# m101-psu-dcdc.net
KiCad netlist of a schematic drawn in EAGLE
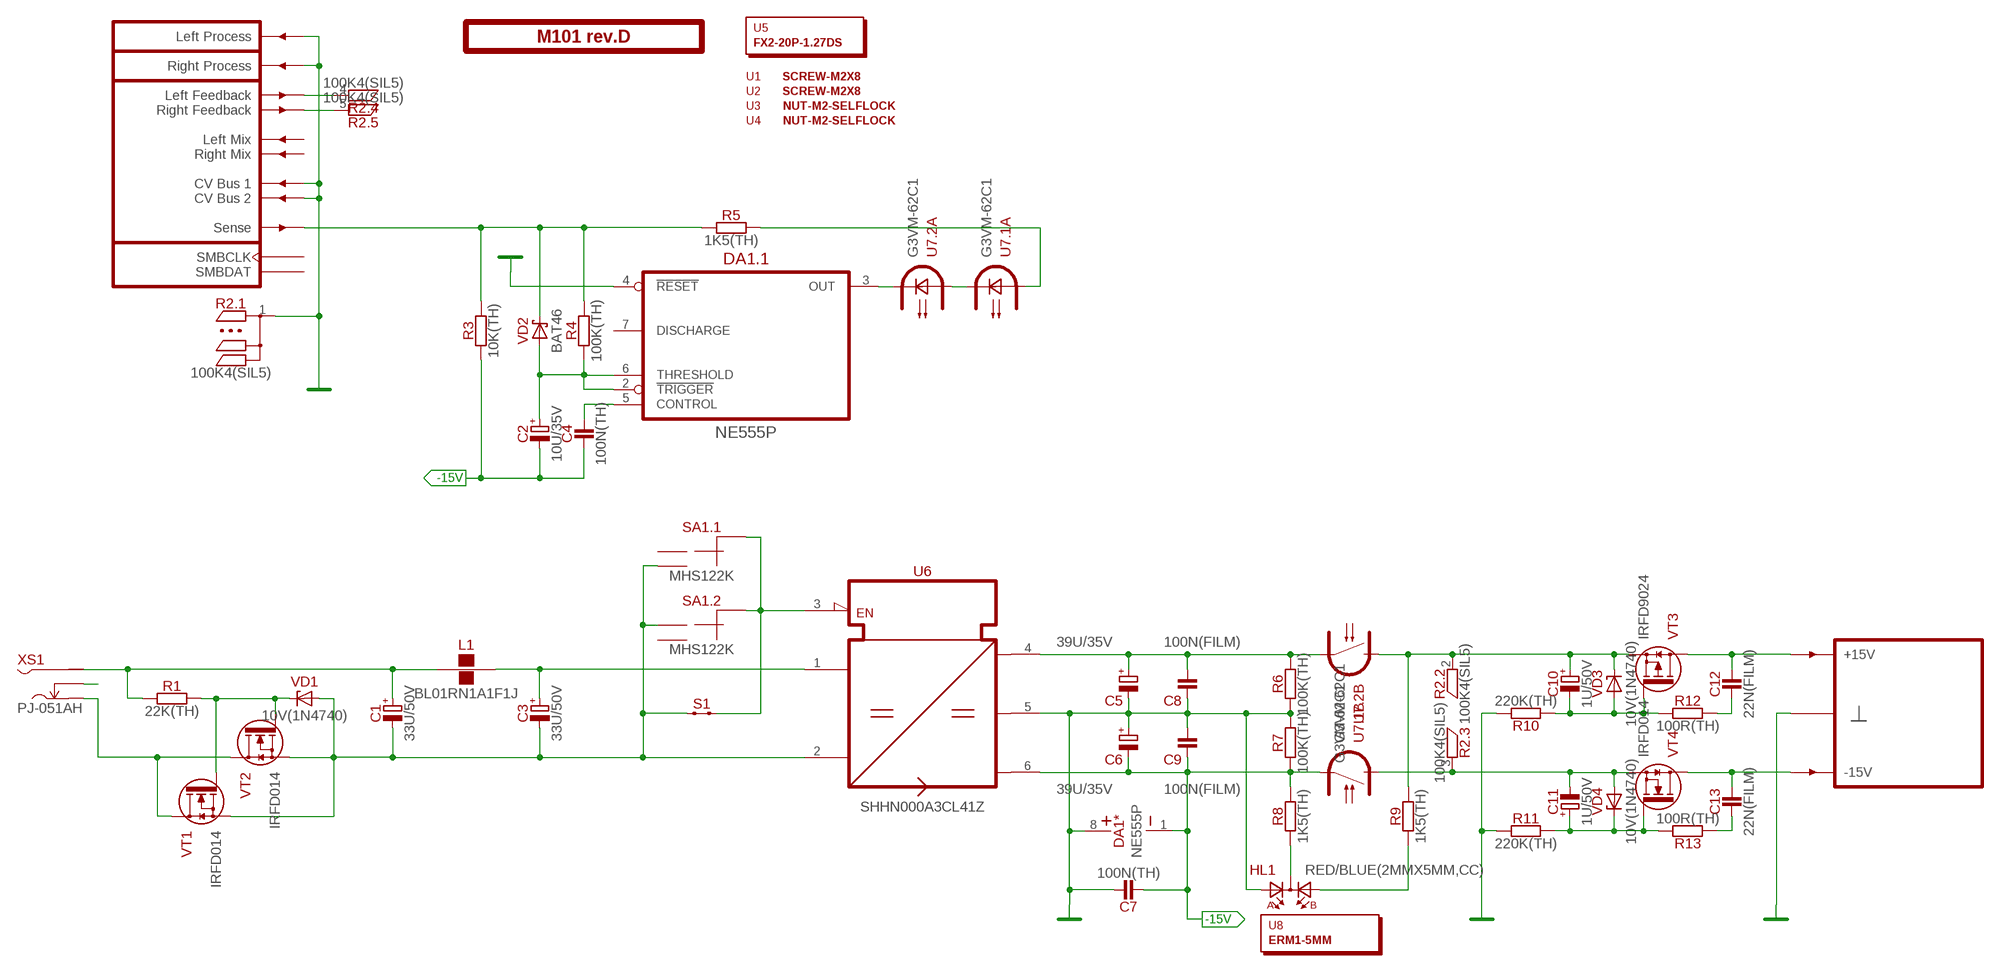
[diagram p0: schematic, sheet 1]

(export (version "E")
  (design (tool "Eeschema 10.0.6"))
  (components
    (comp (ref "C1")
      (value "33U/50V")
      (footprint "eagle-import:E3,5-8")
      (libsource (lib "eagle-import") (part "?33U/50V"))
    )
    (comp (ref "C2")
      (value "10U/35V")
      (footprint "eagle-import:E2-5")
      (libsource (lib "eagle-import") (part "?10U/35V"))
    )
    (comp (ref "C3")
      (value "33U/50V")
      (footprint "eagle-import:E3,5-8")
      (libsource (lib "eagle-import") (part "?33U/50V"))
    )
    (comp (ref "C4")
      (value "100N(TH)")
      (footprint "eagle-import:C050-024X044")
      (libsource (lib "eagle-import") (part "?100N(TH)"))
    )
    (comp (ref "C5")
      (value "39U/35V")
      (footprint "eagle-import:E3,5-8")
      (libsource (lib "eagle-import") (part "?39U/35V"))
    )
    (comp (ref "C6")
      (value "39U/35V")
      (footprint "eagle-import:E3,5-8")
      (libsource (lib "eagle-import") (part "?39U/35V"))
    )
    (comp (ref "C7")
      (value "100N(TH)")
      (footprint "eagle-import:C050-024X044")
      (libsource (lib "eagle-import") (part "?100N(TH)"))
    )
    (comp (ref "C8")
      (value "100N(FILM)")
      (footprint "eagle-import:C050-025X075")
      (libsource (lib "eagle-import") (part "?100N(FILM)"))
    )
    (comp (ref "C9")
      (value "100N(FILM)")
      (footprint "eagle-import:C050-025X075")
      (libsource (lib "eagle-import") (part "?100N(FILM)"))
    )
    (comp (ref "C10")
      (value "1U/50V")
      (footprint "eagle-import:E1,5-4")
      (libsource (lib "eagle-import") (part "?1U/50V"))
    )
    (comp (ref "C11")
      (value "1U/50V")
      (footprint "eagle-import:E1,5-4")
      (libsource (lib "eagle-import") (part "?1U/50V"))
    )
    (comp (ref "C12")
      (value "22N(FILM)")
      (footprint "eagle-import:C050-025X075")
      (libsource (lib "eagle-import") (part "?22N(FILM)"))
    )
    (comp (ref "C13")
      (value "22N(FILM)")
      (footprint "eagle-import:C050-025X075")
      (libsource (lib "eagle-import") (part "?22N(FILM)"))
    )
    (comp (ref "DA1")
      (value "NE555P")
      (footprint "eagle-import:DIP-8")
      (libsource (lib "eagle-import") (part "NE555?P"))
    )
    (comp (ref "HL1")
      (value "RED/BLUE(2MMX5MM,CC)")
      (footprint "eagle-import:LED2X5-3PIN")
      (libsource (lib "eagle-import") (part "?(2MMX5MM,CC)RED/BLUE"))
    )
    (comp (ref "L1")
      (value "BL01RN1A1F1J")
      (footprint "eagle-import:BL01RN1A")
      (libsource (lib "eagle-import") (part "BL01RN1A?1F1J"))
    )
    (comp (ref "PCB1")
      (value "M101 rev.D")
      (footprint "eagle-import:ST2-BOARD-50-PSU")
      (libsource (lib "eagle-import") (part "ST2-BOARD-50-PSU"))
    )
    (comp (ref "R1")
      (value "22K(TH)")
      (footprint "eagle-import:R-0207_10")
      (libsource (lib "eagle-import") (part "?22K(TH)"))
    )
    (comp (ref "R2")
      (value "100K4(SIL5)")
      (footprint "eagle-import:R-SIL5")
      (libsource (lib "eagle-import") (part "?4(SIL5)100K"))
    )
    (comp (ref "R3")
      (value "10K(TH)")
      (footprint "eagle-import:R-0207_10")
      (libsource (lib "eagle-import") (part "?10K(TH)"))
    )
    (comp (ref "R4")
      (value "100K(TH)")
      (footprint "eagle-import:R-0207_10")
      (libsource (lib "eagle-import") (part "?100K(TH)"))
    )
    (comp (ref "R5")
      (value "1K5(TH)")
      (footprint "eagle-import:R-0207_10")
      (libsource (lib "eagle-import") (part "?1K5(TH)"))
    )
    (comp (ref "R6")
      (value "100K(TH)")
      (footprint "eagle-import:R-0207_10")
      (libsource (lib "eagle-import") (part "?100K(TH)"))
    )
    (comp (ref "R7")
      (value "100K(TH)")
      (footprint "eagle-import:R-0207_10")
      (libsource (lib "eagle-import") (part "?100K(TH)"))
    )
    (comp (ref "R8")
      (value "1K5(TH)")
      (footprint "eagle-import:R-0207_10")
      (libsource (lib "eagle-import") (part "?1K5(TH)"))
    )
    (comp (ref "R9")
      (value "1K5(TH)")
      (footprint "eagle-import:R-0207_10")
      (libsource (lib "eagle-import") (part "?1K5(TH)"))
    )
    (comp (ref "R10")
      (value "220K(TH)")
      (footprint "eagle-import:R-0207_10")
      (libsource (lib "eagle-import") (part "?220K(TH)"))
    )
    (comp (ref "R11")
      (value "220K(TH)")
      (footprint "eagle-import:R-0207_10")
      (libsource (lib "eagle-import") (part "?220K(TH)"))
    )
    (comp (ref "R12")
      (value "100R(TH)")
      (footprint "eagle-import:R-0207_10")
      (libsource (lib "eagle-import") (part "?100R(TH)"))
    )
    (comp (ref "R13")
      (value "100R(TH)")
      (footprint "eagle-import:R-0207_10")
      (libsource (lib "eagle-import") (part "?100R(TH)"))
    )
    (comp (ref "S1")
      (value "JUMPER-1POS-SOLDER")
      (footprint "eagle-import:JP1-SOLDER")
      (libsource (lib "eagle-import") (part "JUMPER-1POS-SOLDER"))
    )
    (comp (ref "SA1")
      (value "MHS122K")
      (footprint "eagle-import:APEM-MHS122K")
      (libsource (lib "eagle-import") (part "MHS122K"))
    )
    (comp (ref "U1")
      (value "SCREW-M2X8")
      (footprint "eagle-import:EMPTY")
      (libsource (lib "eagle-import") (part "?SCREW-M2X8"))
    )
    (comp (ref "U2")
      (value "SCREW-M2X8")
      (footprint "eagle-import:EMPTY")
      (libsource (lib "eagle-import") (part "?SCREW-M2X8"))
    )
    (comp (ref "U3")
      (value "NUT-M2-SELFLOCK")
      (footprint "eagle-import:EMPTY")
      (libsource (lib "eagle-import") (part "?NUT-M2-SELFLOCK"))
    )
    (comp (ref "U4")
      (value "NUT-M2-SELFLOCK")
      (footprint "eagle-import:EMPTY")
      (libsource (lib "eagle-import") (part "?NUT-M2-SELFLOCK"))
    )
    (comp (ref "U5")
      (value "FX2-20P-1.27DS")
      (footprint "eagle-import:EMPTY")
      (libsource (lib "eagle-import") (part "?FX2-20P-1.27DS"))
    )
    (comp (ref "U6")
      (value "SHHN000A3CL41Z")
      (footprint "eagle-import:DC_DC-C1")
      (libsource (lib "eagle-import") (part "SHHN000A3CL41Z"))
    )
    (comp (ref "U7")
      (value "G3VM-62C1")
      (footprint "eagle-import:DIL08")
      (libsource (lib "eagle-import") (part "G3VM-?2C61"))
    )
    (comp (ref "U8")
      (value "ERM1-5MM")
      (footprint "eagle-import:EMPTY")
      (libsource (lib "eagle-import") (part "?ERM1-5MM"))
    )
    (comp (ref "VD1")
      (value "10V(1N4740)")
      (footprint "eagle-import:DO41-10")
      (libsource (lib "eagle-import") (part "?10V(1N4740)"))
    )
    (comp (ref "VD2")
      (value "BAT46")
      (footprint "eagle-import:DO35-7")
      (libsource (lib "eagle-import") (part "?BAT46"))
    )
    (comp (ref "VD3")
      (value "10V(1N4740)")
      (footprint "eagle-import:DO41-10")
      (libsource (lib "eagle-import") (part "?10V(1N4740)"))
    )
    (comp (ref "VD4")
      (value "10V(1N4740)")
      (footprint "eagle-import:DO41-10")
      (libsource (lib "eagle-import") (part "?10V(1N4740)"))
    )
    (comp (ref "VT1")
      (value "IRFD014")
      (footprint "eagle-import:HVMDIP-4")
      (libsource (lib "eagle-import") (part "IRFD014"))
    )
    (comp (ref "VT2")
      (value "IRFD014")
      (footprint "eagle-import:HVMDIP-4")
      (libsource (lib "eagle-import") (part "IRFD014"))
    )
    (comp (ref "VT3")
      (value "IRFD9024")
      (footprint "eagle-import:HVMDIP-4")
      (libsource (lib "eagle-import") (part "IRFD9024"))
    )
    (comp (ref "VT4")
      (value "IRFD014")
      (footprint "eagle-import:HVMDIP-4")
      (libsource (lib "eagle-import") (part "IRFD014"))
    )
    (comp (ref "XS1")
      (value "PJ-051AH")
      (footprint "eagle-import:PJ-051AH")
      (libsource (lib "eagle-import") (part "PJ-051?AH"))
    )
  )
  (nets
    (net (code "1") (name "-15V") (class "Default")
      (node (ref "C2") (pin "-") (pinfunction "-_-") (pintype "passive"))
      (node (ref "C4") (pin "1") (pinfunction "1_1") (pintype "passive"))
      (node (ref "C6") (pin "-") (pinfunction "-_-") (pintype "passive"))
      (node (ref "C7") (pin "1") (pinfunction "1_1") (pintype "passive"))
      (node (ref "C9") (pin "1") (pinfunction "1_1") (pintype "passive"))
      (node (ref "DA1") (pin "1") (pinfunction "V-_1") (pintype "power_in"))
      (node (ref "R3") (pin "1") (pinfunction "1_1") (pintype "passive"))
      (node (ref "R7") (pin "1") (pinfunction "1_1") (pintype "passive"))
      (node (ref "R8") (pin "2") (pinfunction "2_2") (pintype "passive"))
      (node (ref "U6") (pin "6") (pinfunction "V-_6") (pintype "power_in"))
      (node (ref "U7") (pin "7") (pinfunction "S2_7") (pintype "passive"))
    )
    (net (code "2") (name "GND") (class "Default")
      (node (ref "C5") (pin "-") (pinfunction "-_-") (pintype "passive"))
      (node (ref "C6") (pin "+") (pinfunction "+_+") (pintype "passive"))
      (node (ref "C7") (pin "2") (pinfunction "2_2") (pintype "passive"))
      (node (ref "C8") (pin "1") (pinfunction "1_1") (pintype "passive"))
      (node (ref "C9") (pin "2") (pinfunction "2_2") (pintype "passive"))
      (node (ref "DA1") (pin "4") (pinfunction "~{RESET}_4") (pintype "input"))
      (node (ref "DA1") (pin "8") (pinfunction "V+_8") (pintype "power_in"))
      (node (ref "HL1") (pin "A1") (pinfunction "A1_A1") (pintype "passive"))
      (node (ref "PCB1") (pin "ACV1'") (pinfunction "CV1'_ACV1'") (pintype "bidirectional"))
      (node (ref "PCB1") (pin "ACV2'") (pinfunction "CV2'_ACV2'") (pintype "bidirectional"))
      (node (ref "PCB1") (pin "B4'") (pinfunction "GND_B4'") (pintype "bidirectional"))
      (node (ref "PCB1") (pin "B5'") (pinfunction "GND_B5'") (pintype "bidirectional"))
      (node (ref "PCB1") (pin "B6'") (pinfunction "GND_B6'") (pintype "bidirectional"))
      (node (ref "PCB1") (pin "B7'") (pinfunction "GND_B7'") (pintype "bidirectional"))
      (node (ref "PCB1") (pin "B8'") (pinfunction "GND_B8'") (pintype "bidirectional"))
      (node (ref "PCB1") (pin "BOUTL'") (pinfunction "OUTL_BOUTL'") (pintype "bidirectional"))
      (node (ref "PCB1") (pin "BOUTR'") (pinfunction "OUTR_BOUTR'") (pintype "bidirectional"))
      (node (ref "R10") (pin "2") (pinfunction "2_2") (pintype "passive"))
      (node (ref "R11") (pin "2") (pinfunction "2_2") (pintype "passive"))
      (node (ref "R2") (pin "1") (pinfunction "R_1") (pintype "passive"))
      (node (ref "R6") (pin "1") (pinfunction "1_1") (pintype "passive"))
      (node (ref "R7") (pin "2") (pinfunction "2_2") (pintype "passive"))
      (node (ref "U6") (pin "5") (pinfunction "GND_5") (pintype "power_in"))
    )
    (net (code "3") (name "Net-(C12-Pad1)") (class "Default")
      (node (ref "C12") (pin "1") (pinfunction "1_1") (pintype "passive"))
      (node (ref "R12") (pin "2") (pinfunction "2_2") (pintype "passive"))
    )
    (net (code "4") (name "Net-(C12-Pad2)") (class "Default")
      (node (ref "C12") (pin "2") (pinfunction "2_2") (pintype "passive"))
      (node (ref "PCB1") (pin "A+15'") (pinfunction "P+15V_A+15'") (pintype "bidirectional"))
      (node (ref "PCB1") (pin "B+15'") (pinfunction "P+15V_B+15'") (pintype "bidirectional"))
      (node (ref "VT3") (pin "1") (pinfunction "D_1") (pintype "bidirectional"))
      (node (ref "VT3") (pin "2") (pinfunction "D_2") (pintype "bidirectional"))
    )
    (net (code "5") (name "Net-(C13-Pad1)") (class "Default")
      (node (ref "C13") (pin "1") (pinfunction "1_1") (pintype "passive"))
      (node (ref "PCB1") (pin "A-15'") (pinfunction "P-15V_A-15'") (pintype "bidirectional"))
      (node (ref "PCB1") (pin "B-15'") (pinfunction "P-15V_B-15'") (pintype "bidirectional"))
      (node (ref "VT4") (pin "1") (pinfunction "D_1") (pintype "bidirectional"))
      (node (ref "VT4") (pin "2") (pinfunction "D_2") (pintype "bidirectional"))
    )
    (net (code "6") (name "Net-(C13-Pad2)") (class "Default")
      (node (ref "C13") (pin "2") (pinfunction "2_2") (pintype "passive"))
      (node (ref "R13") (pin "2") (pinfunction "2_2") (pintype "passive"))
    )
    (net (code "7") (name "Net-(DA1B-CONTROL)") (class "Default")
      (node (ref "C4") (pin "2") (pinfunction "2_2") (pintype "passive"))
      (node (ref "DA1") (pin "5") (pinfunction "CONTROL_5") (pintype "bidirectional"))
    )
    (net (code "8") (name "Net-(DA1B-OUT)") (class "Default")
      (node (ref "DA1") (pin "3") (pinfunction "OUT_3") (pintype "bidirectional"))
      (node (ref "U7") (pin "4") (pinfunction "C_4") (pintype "passive"))
    )
    (net (code "9") (name "Net-(DA1B-THRESHOLD)") (class "Default")
      (node (ref "C2") (pin "+") (pinfunction "+_+") (pintype "passive"))
      (node (ref "DA1") (pin "2") (pinfunction "~{TRIGGER}_2") (pintype "bidirectional"))
      (node (ref "DA1") (pin "6") (pinfunction "THRESHOLD_6") (pintype "bidirectional"))
      (node (ref "R4") (pin "1") (pinfunction "1_1") (pintype "passive"))
      (node (ref "VD2") (pin "A") (pinfunction "A_A") (pintype "passive"))
    )
    (net (code "10") (name "Net-(HL1-PadA2)") (class "Default")
      (node (ref "HL1") (pin "A2") (pinfunction "A2_A2") (pintype "passive"))
      (node (ref "R9") (pin "1") (pinfunction "1_1") (pintype "passive"))
    )
    (net (code "11") (name "Net-(HL1-PadK)") (class "Default")
      (node (ref "HL1") (pin "K") (pinfunction "K_K") (pintype "passive"))
      (node (ref "R8") (pin "1") (pinfunction "1_1") (pintype "passive"))
    )
    (net (code "12") (name "Net-(PCB1D-LFBK')") (class "Default")
      (node (ref "PCB1") (pin "ALFBK'") (pinfunction "LFBK'_ALFBK'") (pintype "bidirectional"))
      (node (ref "R2") (pin "4") (pinfunction "R_4") (pintype "passive"))
    )
    (net (code "13") (name "Net-(PCB1D-RFBK')") (class "Default")
      (node (ref "PCB1") (pin "ARFBK'") (pinfunction "RFBK'_ARFBK'") (pintype "bidirectional"))
      (node (ref "R2") (pin "5") (pinfunction "R_5") (pintype "passive"))
    )
    (net (code "14") (name "Net-(PCB1D-SENSE')") (class "Default")
      (node (ref "PCB1") (pin "BSENSE'") (pinfunction "SENSE'_BSENSE'") (pintype "bidirectional"))
      (node (ref "R3") (pin "2") (pinfunction "2_2") (pintype "passive"))
      (node (ref "R4") (pin "2") (pinfunction "2_2") (pintype "passive"))
      (node (ref "R5") (pin "1") (pinfunction "1_1") (pintype "passive"))
      (node (ref "VD2") (pin "C") (pinfunction "C_C") (pintype "passive"))
    )
    (net (code "15") (name "Net-(R2B-R)") (class "Default")
      (node (ref "C10") (pin "+") (pinfunction "+_+") (pintype "passive"))
      (node (ref "R2") (pin "2") (pinfunction "R_2") (pintype "passive"))
      (node (ref "R9") (pin "2") (pinfunction "2_2") (pintype "passive"))
      (node (ref "U7") (pin "6") (pinfunction "S1_6") (pintype "passive"))
      (node (ref "VD3") (pin "C") (pinfunction "C_C") (pintype "passive"))
      (node (ref "VT3") (pin "4") (pinfunction "S_4") (pintype "bidirectional"))
    )
    (net (code "16") (name "Net-(R2C-R)") (class "Default")
      (node (ref "C11") (pin "-") (pinfunction "-_-") (pintype "passive"))
      (node (ref "R2") (pin "3") (pinfunction "R_3") (pintype "passive"))
      (node (ref "U7") (pin "8") (pinfunction "S1_8") (pintype "passive"))
      (node (ref "VD4") (pin "A") (pinfunction "A_A") (pintype "passive"))
      (node (ref "VT4") (pin "4") (pinfunction "S_4") (pintype "bidirectional"))
    )
    (net (code "17") (name "Net-(SA1A-CM)") (class "Default")
      (node (ref "S1") (pin "2") (pinfunction "2_2") (pintype "passive"))
      (node (ref "SA1") (pin "CMN") (pinfunction "CM_CMN") (pintype "passive"))
      (node (ref "SA1") (pin "CMN'") (pinfunction "CM_CMN'") (pintype "passive"))
      (node (ref "U6") (pin "3") (pinfunction "EN_3") (pintype "bidirectional"))
    )
    (net (code "18") (name "Net-(SA1B-1)") (class "Default")
      (node (ref "C1") (pin "-") (pinfunction "-_-") (pintype "passive"))
      (node (ref "C3") (pin "-") (pinfunction "-_-") (pintype "passive"))
      (node (ref "S1") (pin "1") (pinfunction "1_1") (pintype "passive"))
      (node (ref "SA1") (pin "1'") (pinfunction "1_1'") (pintype "passive"))
      (node (ref "SA1") (pin "2") (pinfunction "2_2") (pintype "passive"))
      (node (ref "U6") (pin "2") (pinfunction "IN-_2") (pintype "power_in"))
      (node (ref "VD1") (pin "A") (pinfunction "A_A") (pintype "passive"))
      (node (ref "VT1") (pin "4") (pinfunction "S_4") (pintype "bidirectional"))
      (node (ref "VT2") (pin "4") (pinfunction "S_4") (pintype "bidirectional"))
    )
    (net (code "19") (name "Net-(U6-IN+)") (class "Default")
      (node (ref "C3") (pin "+") (pinfunction "+_+") (pintype "passive"))
      (node (ref "L1") (pin "2") (pinfunction "2_2") (pintype "passive"))
      (node (ref "U6") (pin "1") (pinfunction "IN+_1") (pintype "power_in"))
    )
    (net (code "20") (name "Net-(U6-V+)") (class "Default")
      (node (ref "C5") (pin "+") (pinfunction "+_+") (pintype "passive"))
      (node (ref "C8") (pin "2") (pinfunction "2_2") (pintype "passive"))
      (node (ref "R6") (pin "2") (pinfunction "2_2") (pintype "passive"))
      (node (ref "U6") (pin "4") (pinfunction "V+_4") (pintype "power_in"))
      (node (ref "U7") (pin "5") (pinfunction "S2_5") (pintype "passive"))
    )
    (net (code "21") (name "Net-(U7A-A)") (class "Default")
      (node (ref "R5") (pin "2") (pinfunction "2_2") (pintype "passive"))
      (node (ref "U7") (pin "1") (pinfunction "A_1") (pintype "passive"))
    )
    (net (code "22") (name "Net-(U7A-C)") (class "Default")
      (node (ref "U7") (pin "2") (pinfunction "C_2") (pintype "passive"))
      (node (ref "U7") (pin "3") (pinfunction "A_3") (pintype "passive"))
    )
    (net (code "23") (name "Net-(VT1-G)") (class "Default")
      (node (ref "R1") (pin "2") (pinfunction "2_2") (pintype "passive"))
      (node (ref "VD1") (pin "C") (pinfunction "C_C") (pintype "passive"))
      (node (ref "VT1") (pin "3") (pinfunction "G_3") (pintype "bidirectional"))
      (node (ref "VT2") (pin "3") (pinfunction "G_3") (pintype "bidirectional"))
    )
    (net (code "24") (name "Net-(VT3-G)") (class "Default")
      (node (ref "C10") (pin "-") (pinfunction "-_-") (pintype "passive"))
      (node (ref "R10") (pin "1") (pinfunction "1_1") (pintype "passive"))
      (node (ref "R12") (pin "1") (pinfunction "1_1") (pintype "passive"))
      (node (ref "VD3") (pin "A") (pinfunction "A_A") (pintype "passive"))
      (node (ref "VT3") (pin "3") (pinfunction "G_3") (pintype "bidirectional"))
    )
    (net (code "25") (name "Net-(VT4-G)") (class "Default")
      (node (ref "C11") (pin "+") (pinfunction "+_+") (pintype "passive"))
      (node (ref "R11") (pin "1") (pinfunction "1_1") (pintype "passive"))
      (node (ref "R13") (pin "1") (pinfunction "1_1") (pintype "passive"))
      (node (ref "VD4") (pin "C") (pinfunction "C_C") (pintype "passive"))
      (node (ref "VT4") (pin "3") (pinfunction "G_3") (pintype "bidirectional"))
    )
    (net (code "26") (name "Net-(XS1-P)") (class "Default")
      (node (ref "C1") (pin "+") (pinfunction "+_+") (pintype "passive"))
      (node (ref "L1") (pin "1") (pinfunction "1_1") (pintype "passive"))
      (node (ref "R1") (pin "1") (pinfunction "1_1") (pintype "passive"))
      (node (ref "XS1") (pin "1") (pinfunction "P_1") (pintype "passive"))
    )
    (net (code "27") (name "Net-(XS1-S)") (class "Default")
      (node (ref "VT1") (pin "1") (pinfunction "D_1") (pintype "bidirectional"))
      (node (ref "VT1") (pin "2") (pinfunction "D_2") (pintype "bidirectional"))
      (node (ref "VT2") (pin "1") (pinfunction "D_1") (pintype "bidirectional"))
      (node (ref "VT2") (pin "2") (pinfunction "D_2") (pintype "bidirectional"))
      (node (ref "XS1") (pin "3") (pinfunction "S_3") (pintype "passive"))
    )
    (net (code "28") (name "unconnected-(DA1B-DISCHARGE-Pad7)") (class "Default")
      (node (ref "DA1") (pin "7") (pinfunction "DISCHARGE_7") (pintype "bidirectional"))
    )
    (net (code "29") (name "unconnected-(PCB1D-LMIX'-PadALMIX')") (class "Default")
      (node (ref "PCB1") (pin "ALMIX'") (pinfunction "LMIX'_ALMIX'") (pintype "bidirectional"))
    )
    (net (code "30") (name "unconnected-(PCB1D-RMIX'-PadARMIX')") (class "Default")
      (node (ref "PCB1") (pin "ARMIX'") (pinfunction "RMIX'_ARMIX'") (pintype "bidirectional"))
    )
    (net (code "31") (name "unconnected-(PCB1E-SMBCLK-PadASMBCLK')") (class "Default")
      (node (ref "PCB1") (pin "ASMBCLK'") (pinfunction "SMBCLK_ASMBCLK'") (pintype "bidirectional"))
    )
    (net (code "32") (name "unconnected-(PCB1E-SMBDAT-PadASMBDAT')") (class "Default")
      (node (ref "PCB1") (pin "ASMBDAT'") (pinfunction "SMBDAT_ASMBDAT'") (pintype "bidirectional"))
    )
    (net (code "33") (name "unconnected-(SA1-Pad1)") (class "Default")
      (node (ref "SA1") (pin "1") (pinfunction "1_1") (pintype "passive"))
    )
    (net (code "34") (name "unconnected-(SA1B-2-Pad2')") (class "Default")
      (node (ref "SA1") (pin "2'") (pinfunction "2_2'") (pintype "passive"))
    )
    (net (code "35") (name "unconnected-(XS1-SS-Pad2)") (class "Default")
      (node (ref "XS1") (pin "2") (pinfunction "SS_2") (pintype "passive"))
    )
  )
)
